# PDM_Microphone_Array_Prototype.net
KiCad netlist of a schematic drawn in EAGLE
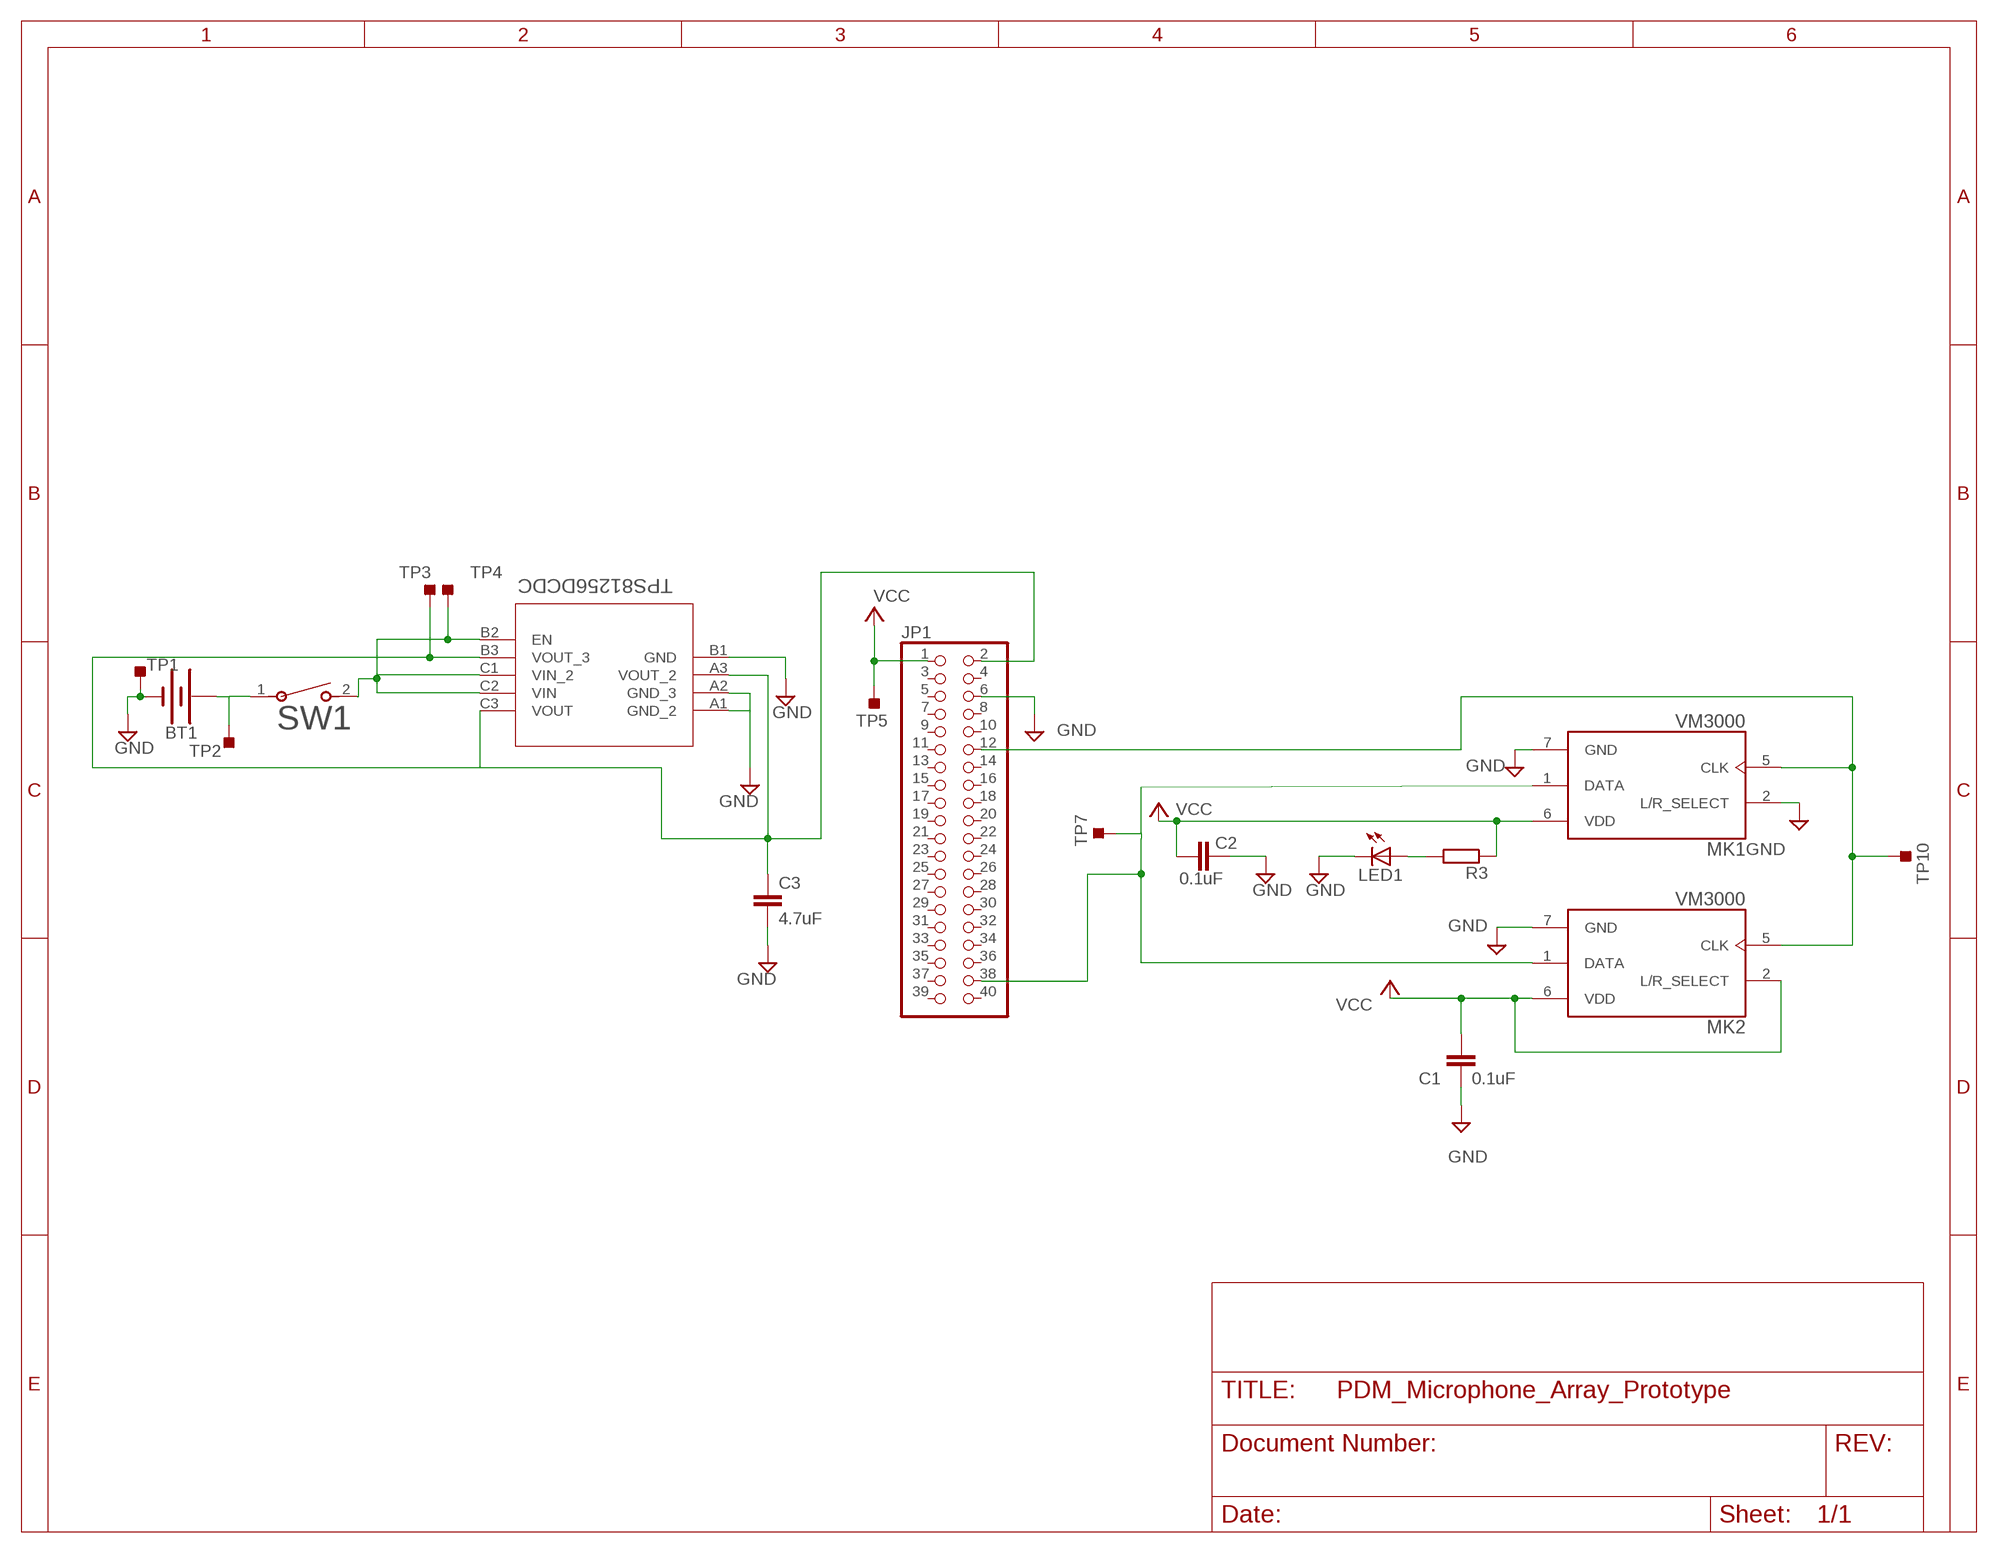
[diagram p0: schematic, sheet 1]

(export (version "E")
  (design (tool "Eeschema 10.0.6"))
  (components
    (comp (ref "BT1")
      (value "BATTERY-18650")
      (footprint "eagle-import:BATTERY_18650-HOLDER")
      (libsource (lib "eagle-import") (part "BATTERY-18650"))
    )
    (comp (ref "C1")
      (value "0.1uF")
      (footprint "eagle-import:0402")
      (libsource (lib "eagle-import") (part "0.1UF-0402-6.3V-10%-X7R"))
    )
    (comp (ref "C2")
      (value "0.1uF")
      (footprint "eagle-import:0402")
      (libsource (lib "eagle-import") (part "0.1UF-0402-6.3V-10%-X7R"))
    )
    (comp (ref "C3")
      (value "4.7uF")
      (footprint "eagle-import:1206")
      (libsource (lib "eagle-import") (part "4.7UF-1206-16V-(+80/-20%)"))
    )
    (comp (ref "JP1")
      (value "PINHD-2X20")
      (footprint "eagle-import:2X20")
      (libsource (lib "eagle-import") (part "PINHD-2X20"))
    )
    (comp (ref "LED1")
      (value "LEDCHIPLED_0805")
      (footprint "eagle-import:CHIPLED_0805")
      (libsource (lib "eagle-import") (part "LEDCHIPLED_0805"))
    )
    (comp (ref "MK1")
      (value "VM3000")
      (footprint "eagle-import:MIC_VM3000")
      (fields (field (name "MF") "Vesper Technologies Inc."))
      (libsource (lib "eagle-import") (part "VM3000"))
    )
    (comp (ref "MK2")
      (value "VM3000")
      (footprint "eagle-import:MIC_VM3000")
      (fields (field (name "MF") "Vesper Technologies Inc."))
      (libsource (lib "eagle-import") (part "VM3000"))
    )
    (comp (ref "R3")
      (value "R-EU_R0805")
      (footprint "eagle-import:R0805")
      (libsource (lib "eagle-import") (part "R-EU_R0805"))
    )
    (comp (ref "SW1")
      (value "GF-123-0054")
      (footprint "eagle-import:SW2_GF-123-0054_CWI")
      (fields (field (name "COPYRIGHT") "Copyright (C) 2018 Accelerated Designs. All rights reserved"))
      (libsource (lib "eagle-import") (part "GF-123-0054"))
    )
    (comp (ref "TP1")
      (value "TESTPOINT_TPS-PAD-036")
      (footprint "eagle-import:TESTPOINT_PAD-036")
      (libsource (lib "eagle-import") (part "TESTPOINT_TPS-PAD-036"))
    )
    (comp (ref "TP2")
      (value "TESTPOINT_TPS-PAD-036")
      (footprint "eagle-import:TESTPOINT_PAD-036")
      (libsource (lib "eagle-import") (part "TESTPOINT_TPS-PAD-036"))
    )
    (comp (ref "TP3")
      (value "TESTPOINT_TPS-PAD-036")
      (footprint "eagle-import:TESTPOINT_PAD-036")
      (libsource (lib "eagle-import") (part "TESTPOINT_TPS-PAD-036"))
    )
    (comp (ref "TP4")
      (value "TESTPOINT_TPS-PAD-036")
      (footprint "eagle-import:TESTPOINT_PAD-036")
      (libsource (lib "eagle-import") (part "TESTPOINT_TPS-PAD-036"))
    )
    (comp (ref "TP5")
      (value "TESTPOINT_TPS-PAD-036")
      (footprint "eagle-import:TESTPOINT_PAD-036")
      (libsource (lib "eagle-import") (part "TESTPOINT_TPS-PAD-036"))
    )
    (comp (ref "TP7")
      (value "TESTPOINT_TPS-PAD-036")
      (footprint "eagle-import:TESTPOINT_PAD-036")
      (libsource (lib "eagle-import") (part "TESTPOINT_TPS-PAD-036"))
    )
    (comp (ref "TP10")
      (value "TESTPOINT_TPS-PAD-036")
      (footprint "eagle-import:TESTPOINT_PAD-036")
      (libsource (lib "eagle-import") (part "TESTPOINT_TPS-PAD-036"))
    )
    (comp (ref "TPS81256DCDC")
      (value "TPS81256SIPRUSIP9_SIP_TEX-L")
      (footprint "eagle-import:USIP9_SIP_TEX-L")
      (fields
        (field (name "MANUFACTURER_PART_NUMBER") "TPS81256SIPR")
        (field (name "COPYRIGHT") "Copyright (C) 2018 Accelerated Designs. All rights reserved")
      )
      (libsource (lib "eagle-import") (part "TPS81256SIPRUSIP9_SIP_TEX-L"))
    )
  )
  (nets
    (net (code "1") (name "GND") (class "Default")
      (node (ref "BT1") (pin "GND@1") (pinfunction "-_GND@1") (pintype "power_in"))
      (node (ref "C1") (pin "2") (pinfunction "2_2") (pintype "passive"))
      (node (ref "C2") (pin "1") (pinfunction "1_1") (pintype "passive"))
      (node (ref "C3") (pin "2") (pinfunction "2_2") (pintype "passive"))
      (node (ref "JP1") (pin "6") (pinfunction "6_6") (pintype "passive"))
      (node (ref "LED1") (pin "C") (pinfunction "C_C") (pintype "passive"))
      (node (ref "MK1") (pin "2") (pinfunction "L/R_SELECT_2") (pintype "input"))
      (node (ref "MK1") (pin "7") (pinfunction "GND_7") (pintype "power_in"))
      (node (ref "MK2") (pin "7") (pinfunction "GND_7") (pintype "power_in"))
      (node (ref "TP1") (pin "1") (pinfunction "TP_1") (pintype "passive"))
      (node (ref "TPS81256DCDC") (pin "A1") (pinfunction "GND_2_A1") (pintype "passive"))
      (node (ref "TPS81256DCDC") (pin "A2") (pinfunction "GND_3_A2") (pintype "passive"))
      (node (ref "TPS81256DCDC") (pin "B1") (pinfunction "GND_B1") (pintype "passive"))
    )
    (net (code "2") (name "Net-(BT1-+)") (class "Default")
      (node (ref "BT1") (pin "PWR@1") (pinfunction "+_PWR@1") (pintype "power_in"))
      (node (ref "SW1") (pin "1") (pinfunction "1_1") (pintype "passive"))
      (node (ref "TP2") (pin "1") (pinfunction "TP_1") (pintype "passive"))
    )
    (net (code "3") (name "Net-(LED1-PadA)") (class "Default")
      (node (ref "LED1") (pin "A") (pinfunction "A_A") (pintype "passive"))
      (node (ref "R3") (pin "2") (pinfunction "2_2") (pintype "passive"))
    )
    (net (code "4") (name "Net-(MK1-CLK)") (class "Default")
      (node (ref "JP1") (pin "12") (pinfunction "12_12") (pintype "passive"))
      (node (ref "MK1") (pin "5") (pinfunction "CLK_5") (pintype "input"))
      (node (ref "MK2") (pin "5") (pinfunction "CLK_5") (pintype "input"))
      (node (ref "TP10") (pin "1") (pinfunction "TP_1") (pintype "passive"))
    )
    (net (code "5") (name "Net-(MK1-DATA)") (class "Default")
      (node (ref "JP1") (pin "38") (pinfunction "38_38") (pintype "passive"))
      (node (ref "MK1") (pin "1") (pinfunction "DATA_1") (pintype "output"))
      (node (ref "MK2") (pin "1") (pinfunction "DATA_1") (pintype "output"))
      (node (ref "TP7") (pin "1") (pinfunction "TP_1") (pintype "passive"))
    )
    (net (code "6") (name "Net-(TP3-TP)") (class "Default")
      (node (ref "C3") (pin "1") (pinfunction "1_1") (pintype "passive"))
      (node (ref "JP1") (pin "2") (pinfunction "2_2") (pintype "passive"))
      (node (ref "TP3") (pin "1") (pinfunction "TP_1") (pintype "passive"))
      (node (ref "TPS81256DCDC") (pin "A3") (pinfunction "VOUT_2_A3") (pintype "output"))
      (node (ref "TPS81256DCDC") (pin "B3") (pinfunction "VOUT_3_B3") (pintype "output"))
      (node (ref "TPS81256DCDC") (pin "C3") (pinfunction "VOUT_C3") (pintype "output"))
    )
    (net (code "7") (name "Net-(TP4-TP)") (class "Default")
      (node (ref "SW1") (pin "2") (pinfunction "2_2") (pintype "passive"))
      (node (ref "TP4") (pin "1") (pinfunction "TP_1") (pintype "passive"))
      (node (ref "TPS81256DCDC") (pin "B2") (pinfunction "EN_B2") (pintype "input"))
      (node (ref "TPS81256DCDC") (pin "C1") (pinfunction "VIN_2_C1") (pintype "power_in"))
      (node (ref "TPS81256DCDC") (pin "C2") (pinfunction "VIN_C2") (pintype "power_in"))
    )
    (net (code "8") (name "VCC") (class "Default")
      (node (ref "C1") (pin "1") (pinfunction "1_1") (pintype "passive"))
      (node (ref "C2") (pin "2") (pinfunction "2_2") (pintype "passive"))
      (node (ref "JP1") (pin "1") (pinfunction "1_1") (pintype "passive"))
      (node (ref "MK1") (pin "6") (pinfunction "VDD_6") (pintype "power_in"))
      (node (ref "MK2") (pin "2") (pinfunction "L/R_SELECT_2") (pintype "input"))
      (node (ref "MK2") (pin "6") (pinfunction "VDD_6") (pintype "power_in"))
      (node (ref "R3") (pin "1") (pinfunction "1_1") (pintype "passive"))
      (node (ref "TP5") (pin "1") (pinfunction "TP_1") (pintype "passive"))
    )
    (net (code "9") (name "unconnected-(JP1-Pad3)") (class "Default")
      (node (ref "JP1") (pin "3") (pinfunction "3_3") (pintype "passive"))
    )
    (net (code "10") (name "unconnected-(JP1-Pad4)") (class "Default")
      (node (ref "JP1") (pin "4") (pinfunction "4_4") (pintype "passive"))
    )
    (net (code "11") (name "unconnected-(JP1-Pad5)") (class "Default")
      (node (ref "JP1") (pin "5") (pinfunction "5_5") (pintype "passive"))
    )
    (net (code "12") (name "unconnected-(JP1-Pad7)") (class "Default")
      (node (ref "JP1") (pin "7") (pinfunction "7_7") (pintype "passive"))
    )
    (net (code "13") (name "unconnected-(JP1-Pad8)") (class "Default")
      (node (ref "JP1") (pin "8") (pinfunction "8_8") (pintype "passive"))
    )
    (net (code "14") (name "unconnected-(JP1-Pad9)") (class "Default")
      (node (ref "JP1") (pin "9") (pinfunction "9_9") (pintype "passive"))
    )
    (net (code "15") (name "unconnected-(JP1-Pad10)") (class "Default")
      (node (ref "JP1") (pin "10") (pinfunction "10_10") (pintype "passive"))
    )
    (net (code "16") (name "unconnected-(JP1-Pad11)") (class "Default")
      (node (ref "JP1") (pin "11") (pinfunction "11_11") (pintype "passive"))
    )
    (net (code "17") (name "unconnected-(JP1-Pad13)") (class "Default")
      (node (ref "JP1") (pin "13") (pinfunction "13_13") (pintype "passive"))
    )
    (net (code "18") (name "unconnected-(JP1-Pad14)") (class "Default")
      (node (ref "JP1") (pin "14") (pinfunction "14_14") (pintype "passive"))
    )
    (net (code "19") (name "unconnected-(JP1-Pad15)") (class "Default")
      (node (ref "JP1") (pin "15") (pinfunction "15_15") (pintype "passive"))
    )
    (net (code "20") (name "unconnected-(JP1-Pad16)") (class "Default")
      (node (ref "JP1") (pin "16") (pinfunction "16_16") (pintype "passive"))
    )
    (net (code "21") (name "unconnected-(JP1-Pad17)") (class "Default")
      (node (ref "JP1") (pin "17") (pinfunction "17_17") (pintype "passive"))
    )
    (net (code "22") (name "unconnected-(JP1-Pad18)") (class "Default")
      (node (ref "JP1") (pin "18") (pinfunction "18_18") (pintype "passive"))
    )
    (net (code "23") (name "unconnected-(JP1-Pad19)") (class "Default")
      (node (ref "JP1") (pin "19") (pinfunction "19_19") (pintype "passive"))
    )
    (net (code "24") (name "unconnected-(JP1-Pad20)") (class "Default")
      (node (ref "JP1") (pin "20") (pinfunction "20_20") (pintype "passive"))
    )
    (net (code "25") (name "unconnected-(JP1-Pad21)") (class "Default")
      (node (ref "JP1") (pin "21") (pinfunction "21_21") (pintype "passive"))
    )
    (net (code "26") (name "unconnected-(JP1-Pad22)") (class "Default")
      (node (ref "JP1") (pin "22") (pinfunction "22_22") (pintype "passive"))
    )
    (net (code "27") (name "unconnected-(JP1-Pad23)") (class "Default")
      (node (ref "JP1") (pin "23") (pinfunction "23_23") (pintype "passive"))
    )
    (net (code "28") (name "unconnected-(JP1-Pad24)") (class "Default")
      (node (ref "JP1") (pin "24") (pinfunction "24_24") (pintype "passive"))
    )
    (net (code "29") (name "unconnected-(JP1-Pad25)") (class "Default")
      (node (ref "JP1") (pin "25") (pinfunction "25_25") (pintype "passive"))
    )
    (net (code "30") (name "unconnected-(JP1-Pad26)") (class "Default")
      (node (ref "JP1") (pin "26") (pinfunction "26_26") (pintype "passive"))
    )
    (net (code "31") (name "unconnected-(JP1-Pad27)") (class "Default")
      (node (ref "JP1") (pin "27") (pinfunction "27_27") (pintype "passive"))
    )
    (net (code "32") (name "unconnected-(JP1-Pad28)") (class "Default")
      (node (ref "JP1") (pin "28") (pinfunction "28_28") (pintype "passive"))
    )
    (net (code "33") (name "unconnected-(JP1-Pad29)") (class "Default")
      (node (ref "JP1") (pin "29") (pinfunction "29_29") (pintype "passive"))
    )
    (net (code "34") (name "unconnected-(JP1-Pad30)") (class "Default")
      (node (ref "JP1") (pin "30") (pinfunction "30_30") (pintype "passive"))
    )
    (net (code "35") (name "unconnected-(JP1-Pad31)") (class "Default")
      (node (ref "JP1") (pin "31") (pinfunction "31_31") (pintype "passive"))
    )
    (net (code "36") (name "unconnected-(JP1-Pad32)") (class "Default")
      (node (ref "JP1") (pin "32") (pinfunction "32_32") (pintype "passive"))
    )
    (net (code "37") (name "unconnected-(JP1-Pad33)") (class "Default")
      (node (ref "JP1") (pin "33") (pinfunction "33_33") (pintype "passive"))
    )
    (net (code "38") (name "unconnected-(JP1-Pad34)") (class "Default")
      (node (ref "JP1") (pin "34") (pinfunction "34_34") (pintype "passive"))
    )
    (net (code "39") (name "unconnected-(JP1-Pad35)") (class "Default")
      (node (ref "JP1") (pin "35") (pinfunction "35_35") (pintype "passive"))
    )
    (net (code "40") (name "unconnected-(JP1-Pad36)") (class "Default")
      (node (ref "JP1") (pin "36") (pinfunction "36_36") (pintype "passive"))
    )
    (net (code "41") (name "unconnected-(JP1-Pad37)") (class "Default")
      (node (ref "JP1") (pin "37") (pinfunction "37_37") (pintype "passive"))
    )
    (net (code "42") (name "unconnected-(JP1-Pad39)") (class "Default")
      (node (ref "JP1") (pin "39") (pinfunction "39_39") (pintype "passive"))
    )
    (net (code "43") (name "unconnected-(JP1-Pad40)") (class "Default")
      (node (ref "JP1") (pin "40") (pinfunction "40_40") (pintype "passive"))
    )
  )
)
